# USB.net
KiCad netlist of a schematic drawn in Altium Designer
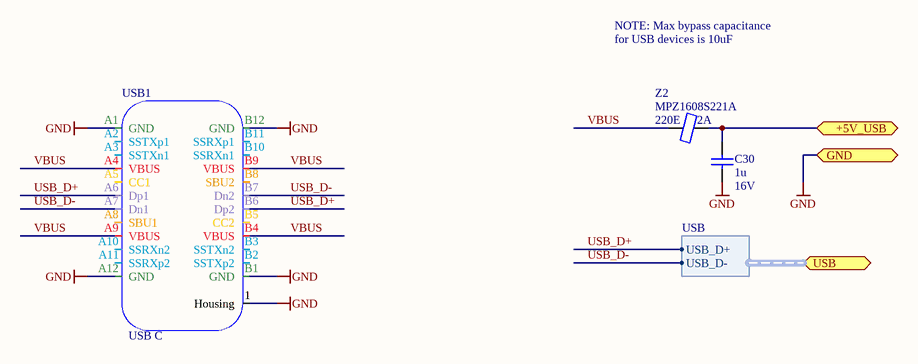
[diagram p0: USB.SchDoc]

(export (version "E")
  (design (tool "Eeschema 10.0.6"))
  (components
    (comp (ref "C30")
      (value "1u")
      (footprint "SMD_CAP_0603")
      (description "1µF ±10% 16V Ceramic Capacitor X7R 0603 (1608 Metric)")
      (fields (field (name "VALUE2") "16V") (field (name "Comment") "C_SMD_CER_1U_16V_10%_X7R_0603"))
      (libsource (lib "AM") (part "C_SMD_CER_1U_16V_10%_X7R_0603"))
    )
    (comp (ref "USB1")
      (value "*")
      (footprint "SMD_CON_USB_TYPEC_VERTICAL_10132328-10011LF")
      (fields (field (name "TYPE") "USB C"))
      (libsource (lib "AM") (part "X_CONNECTOR_USB_TYPEC_VERTICAL"))
    )
    (comp (ref "Z2")
      (value "220E")
      (footprint "SMD_RES_0603")
      (description "Ferrite Beads")
      (fields
        (field (name "TYPE") "MPZ1608S221A")
        (field (name "VALUE2") "2A")
        (field (name "Comment") "Z_SMD_FERRITE_2A_220E@100MHZ_0603")
      )
      (libsource (lib "AM") (part "Z_SMD_FERRITE_2A_220E@100MHZ_0603"))
    )
  )
  (nets
    (net (code "2") (name "/+5V_USB") (class "Default")
      (node (ref "C30") (pin "2") (pinfunction "2_2") (pintype "passive"))
      (node (ref "Z2") (pin "2") (pinfunction "2_2") (pintype "passive"))
    )
    (net (code "3") (name "/USB_D+") (class "Default")
      (node (ref "USB1") (pin "A6") (pinfunction "Dp1_A6") (pintype "passive"))
      (node (ref "USB1") (pin "B6") (pinfunction "Dp2_B6") (pintype "passive"))
    )
    (net (code "4") (name "/USB_D-") (class "Default")
      (node (ref "USB1") (pin "A7") (pinfunction "Dn1_A7") (pintype "passive"))
      (node (ref "USB1") (pin "B7") (pinfunction "Dn2_B7") (pintype "passive"))
    )
    (net (code "5") (name "/VBUS") (class "Default")
      (node (ref "USB1") (pin "A4") (pinfunction "VBUS_A4") (pintype "passive"))
      (node (ref "USB1") (pin "A9") (pinfunction "VBUS_A9") (pintype "passive"))
      (node (ref "USB1") (pin "B4") (pinfunction "VBUS_B4") (pintype "passive"))
      (node (ref "USB1") (pin "B9") (pinfunction "VBUS_B9") (pintype "passive"))
      (node (ref "Z2") (pin "1") (pinfunction "1_1") (pintype "passive"))
    )
    (net (code "7") (name "GND") (class "Default")
      (node (ref "C30") (pin "1") (pinfunction "1_1") (pintype "passive"))
      (node (ref "USB1") (pin "1") (pinfunction "Housing_1") (pintype "passive"))
      (node (ref "USB1") (pin "A1") (pinfunction "GND_A1") (pintype "passive"))
      (node (ref "USB1") (pin "A12") (pinfunction "GND_A12") (pintype "passive"))
      (node (ref "USB1") (pin "B1") (pinfunction "GND_B1") (pintype "passive"))
      (node (ref "USB1") (pin "B12") (pinfunction "GND_B12") (pintype "passive"))
    )
    (net (code "8") (name "unconnected-(USB1-CC1-PadA5)") (class "Default")
      (node (ref "USB1") (pin "A5") (pinfunction "CC1_A5") (pintype "passive"))
    )
    (net (code "9") (name "unconnected-(USB1-CC2-PadB5)") (class "Default")
      (node (ref "USB1") (pin "B5") (pinfunction "CC2_B5") (pintype "passive"))
    )
    (net (code "10") (name "unconnected-(USB1-SBU1-PadA8)") (class "Default")
      (node (ref "USB1") (pin "A8") (pinfunction "SBU1_A8") (pintype "passive"))
    )
    (net (code "11") (name "unconnected-(USB1-SBU2-PadB8)") (class "Default")
      (node (ref "USB1") (pin "B8") (pinfunction "SBU2_B8") (pintype "passive"))
    )
    (net (code "12") (name "unconnected-(USB1-SSRXn1-PadB10)") (class "Default")
      (node (ref "USB1") (pin "B10") (pinfunction "SSRXn1_B10") (pintype "passive"))
    )
    (net (code "13") (name "unconnected-(USB1-SSRXn2-PadA10)") (class "Default")
      (node (ref "USB1") (pin "A10") (pinfunction "SSRXn2_A10") (pintype "passive"))
    )
    (net (code "14") (name "unconnected-(USB1-SSRXp1-PadB11)") (class "Default")
      (node (ref "USB1") (pin "B11") (pinfunction "SSRXp1_B11") (pintype "passive"))
    )
    (net (code "15") (name "unconnected-(USB1-SSRXp2-PadA11)") (class "Default")
      (node (ref "USB1") (pin "A11") (pinfunction "SSRXp2_A11") (pintype "passive"))
    )
    (net (code "16") (name "unconnected-(USB1-SSTXn1-PadA3)") (class "Default")
      (node (ref "USB1") (pin "A3") (pinfunction "SSTXn1_A3") (pintype "passive"))
    )
    (net (code "17") (name "unconnected-(USB1-SSTXn2-PadB3)") (class "Default")
      (node (ref "USB1") (pin "B3") (pinfunction "SSTXn2_B3") (pintype "passive"))
    )
    (net (code "18") (name "unconnected-(USB1-SSTXp1-PadA2)") (class "Default")
      (node (ref "USB1") (pin "A2") (pinfunction "SSTXp1_A2") (pintype "passive"))
    )
    (net (code "19") (name "unconnected-(USB1-SSTXp2-PadB2)") (class "Default")
      (node (ref "USB1") (pin "B2") (pinfunction "SSTXp2_B2") (pintype "passive"))
    )
  )
)
